# MCU.net
KiCad netlist of a schematic drawn in Altium Designer
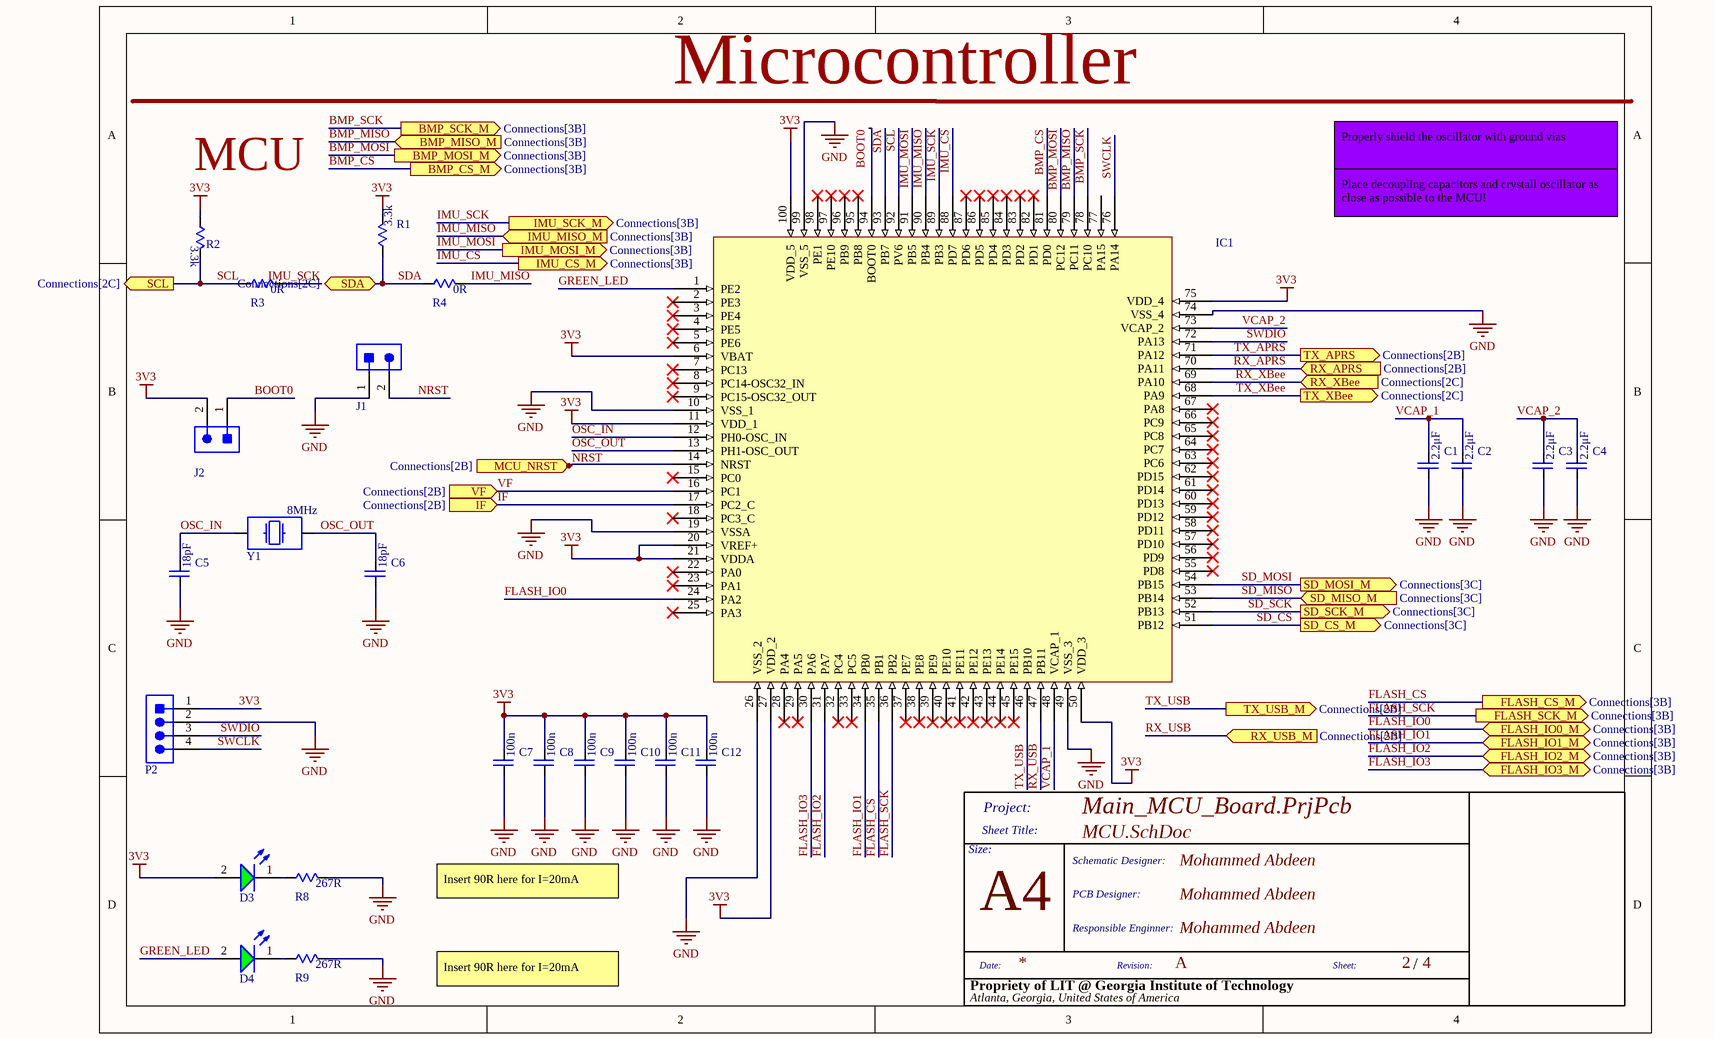
[diagram p0: MCU.SchDoc]

(export (version "E")
  (design (tool "Eeschema 10.0.6"))
  (components
    (comp (ref "C1")
      (value "CL10A225KO8NNNC")
      (footprint "0603-CAP")
      (description "2.2 µF ±10% 16V Ceramic Capacitor X5R 0603 (1608 Metric)")
      (fields (field (name "MANUFACTURER") "Samsung Electro-Mechanics"))
      (libsource (lib "MainMCUSch") (part "CAP-0603-16V"))
    )
    (comp (ref "C2")
      (value "CL10A225KO8NNNC")
      (footprint "0603-CAP")
      (description "2.2 µF ±10% 16V Ceramic Capacitor X5R 0603 (1608 Metric)")
      (fields (field (name "MANUFACTURER") "Samsung Electro-Mechanics"))
      (libsource (lib "MainMCUSch") (part "CAP-0603-16V"))
    )
    (comp (ref "C3")
      (value "CL10A225KO8NNNC")
      (footprint "0603-CAP")
      (description "2.2 µF ±10% 16V Ceramic Capacitor X5R 0603 (1608 Metric)")
      (fields (field (name "MANUFACTURER") "Samsung Electro-Mechanics"))
      (libsource (lib "MainMCUSch") (part "CAP-0603-16V"))
    )
    (comp (ref "C4")
      (value "CL10A225KO8NNNC")
      (footprint "0603-CAP")
      (description "2.2 µF ±10% 16V Ceramic Capacitor X5R 0603 (1608 Metric)")
      (fields (field (name "MANUFACTURER") "Samsung Electro-Mechanics"))
      (libsource (lib "MainMCUSch") (part "CAP-0603-16V"))
    )
    (comp (ref "C5")
      (value "600F180FT250XT")
      (footprint "CAP-0805")
      (description "18 pF ±1% 250V Ceramic Capacitor C0G, NP0 0805 (2012 Metric)")
      (libsource (lib "MainMCUSch") (part "CAP-0805-250V-18pF"))
    )
    (comp (ref "C6")
      (value "600F180FT250XT")
      (footprint "CAP-0805")
      (description "18 pF ±1% 250V Ceramic Capacitor C0G, NP0 0805 (2012 Metric)")
      (libsource (lib "MainMCUSch") (part "CAP-0805-250V-18pF"))
    )
    (comp (ref "C7")
      (value "KGM21NR71E104KT")
      (footprint "CAP-0805")
      (description "0.1 µF ±10% 25V Ceramic Capacitor X7R 0805 (2012 Metric)")
      (libsource (lib "MainMCUSch") (part "CAP-0805-25V-100n"))
    )
    (comp (ref "C8")
      (value "KGM21NR71E104KT")
      (footprint "CAP-0805")
      (description "0.1 µF ±10% 25V Ceramic Capacitor X7R 0805 (2012 Metric)")
      (libsource (lib "MainMCUSch") (part "CAP-0805-25V-100n"))
    )
    (comp (ref "C9")
      (value "KGM21NR71E104KT")
      (footprint "CAP-0805")
      (description "0.1 µF ±10% 25V Ceramic Capacitor X7R 0805 (2012 Metric)")
      (libsource (lib "MainMCUSch") (part "CAP-0805-25V-100n"))
    )
    (comp (ref "C10")
      (value "KGM21NR71E104KT")
      (footprint "CAP-0805")
      (description "0.1 µF ±10% 25V Ceramic Capacitor X7R 0805 (2012 Metric)")
      (libsource (lib "MainMCUSch") (part "CAP-0805-25V-100n"))
    )
    (comp (ref "C11")
      (value "KGM21NR71E104KT")
      (footprint "CAP-0805")
      (description "0.1 µF ±10% 25V Ceramic Capacitor X7R 0805 (2012 Metric)")
      (libsource (lib "MainMCUSch") (part "CAP-0805-25V-100n"))
    )
    (comp (ref "C12")
      (value "KGM21NR71E104KT")
      (footprint "CAP-0805")
      (description "0.1 µF ±10% 25V Ceramic Capacitor X7R 0805 (2012 Metric)")
      (libsource (lib "MainMCUSch") (part "CAP-0805-25V-100n"))
    )
    (comp (ref "D3")
      (value "LTST-C190KGKT")
      (footprint "FP-LTST-C190KGKT-MFG")
      (description "Green 571nm LED Indication - Discrete 2V 0603 (1608 Metric)")
      (libsource (lib "MainMCUSch") (part "LED-0603-Green_"))
    )
    (comp (ref "D4")
      (value "LTST-C190KGKT")
      (footprint "FP-LTST-C190KGKT-MFG")
      (description "Green 571nm LED Indication - Discrete 2V 0603 (1608 Metric)")
      (libsource (lib "MainMCUSch") (part "LED-0603-Green_"))
    )
    (comp (ref "IC1")
      (value "STM32H723VGT6")
      (footprint "QFP50P1600X1600X160-100N")
      (fields (field (name "MANUFACTURER") "STMicroelectronics"))
      (libsource (lib "MainMCUSch") (part "STMH723VGT6"))
    )
    (comp (ref "J1")
      (value "61300211121")
      (footprint "HEADER-2-Pin")
      (description "Connector Header Through Hole 2 position 0.100\" (2.54mm)")
      (fields (field (name "MANUFACTURER") "Würth Elektronik"))
      (libsource (lib "") (part "Header-2-Pin-Male_1"))
    )
    (comp (ref "J2")
      (value "61300211121")
      (footprint "HEADER-2-Pin")
      (description "Connector Header Through Hole 2 position 0.100\" (2.54mm)")
      (fields (field (name "MANUFACTURER") "Würth Elektronik"))
      (libsource (lib "MainMCUSch") (part "Header-2-Pin-Male"))
    )
    (comp (ref "P2")
      (value "22-27-2041")
      (footprint "MOLX-22-27-2041_V")
      (description "Male Header, Pitch 2.54 mm, 1 x 4 Position, Height 11.7 mm, Tail Length 3.56 mm, RoHS, Bulk")
      (fields (field (name "MANUFACTURER") "MOLEX"))
      (libsource (lib "MainMCUSch") (part "Header-4-Pin"))
    )
    (comp (ref "R1")
      (value "ERA-3AEB332V")
      (footprint "0603-RES")
      (description "3.3 kOhms ±0.1% 0.1W, 1/10W Chip Resistor 0603 (1608 Metric) Automotive AEC-Q200 Thin Film")
      (fields (field (name "MANUFACTURER") "Panasonic Electronic Components"))
      (libsource (lib "MainMCUSch") (part "RES-0603-3.3k"))
    )
    (comp (ref "R2")
      (value "ERA-3AEB332V")
      (footprint "0603-RES")
      (description "3.3 kOhms ±0.1% 0.1W, 1/10W Chip Resistor 0603 (1608 Metric) Automotive AEC-Q200 Thin Film")
      (fields (field (name "MANUFACTURER") "Panasonic Electronic Components"))
      (libsource (lib "MainMCUSch") (part "RES-0603-3.3k"))
    )
    (comp (ref "R3")
      (value "ERJ-6GEY0R00V")
      (footprint "0805-RES")
      (description "0 Ohms Jumper Chip Resistor 0805 (2012 Metric) Automotive AEC-Q200 Thick Film")
      (libsource (lib "MainMCUSch") (part "RES-0805-0R"))
    )
    (comp (ref "R4")
      (value "ERJ-6GEY0R00V")
      (footprint "0805-RES")
      (description "0 Ohms Jumper Chip Resistor 0805 (2012 Metric) Automotive AEC-Q200 Thick Film")
      (libsource (lib "MainMCUSch") (part "RES-0805-0R"))
    )
    (comp (ref "R8")
      (value "ERJ-3EKF2670V")
      (footprint "0603-RES")
      (description "267 Ohms ±1% 0.1W, 1/10W Chip Resistor 0603 (1608 Metric) Automotive AEC-Q200 Thick Film")
      (fields (field (name "MANUFACTURER") "Panasonic Electronic Components"))
      (libsource (lib "MainMCUSch") (part "RES-0603-267R"))
    )
    (comp (ref "R9")
      (value "ERJ-3EKF2670V")
      (footprint "0603-RES")
      (description "267 Ohms ±1% 0.1W, 1/10W Chip Resistor 0603 (1608 Metric) Automotive AEC-Q200 Thick Film")
      (fields (field (name "MANUFACTURER") "Panasonic Electronic Components"))
      (libsource (lib "MainMCUSch") (part "RES-0603-267R"))
    )
    (comp (ref "Y1")
      (value "ABLS-8.000MHZ-B2-T")
      (footprint "ABLS-8.000MHZ-B2-T")
      (description "8 MHz ±20ppm Crystal 18pF 80 Ohms HC-49/US")
      (libsource (lib "MainMCUSch") (part "OSC-8MHz-3V3"))
    )
  )
  (nets
    (net (code "1") (name "/BMP_CS") (class "Default")
      (node (ref "IC1") (pin "81") (pinfunction "PD0_81") (pintype "input"))
    )
    (net (code "2") (name "/BMP_MISO") (class "Default")
      (node (ref "IC1") (pin "79") (pinfunction "PC11_79") (pintype "input"))
    )
    (net (code "3") (name "/BMP_MOSI") (class "Default")
      (node (ref "IC1") (pin "80") (pinfunction "PC12_80") (pintype "input"))
    )
    (net (code "4") (name "/BMP_SCK") (class "Default")
      (node (ref "IC1") (pin "78") (pinfunction "PC10_78") (pintype "input"))
    )
    (net (code "5") (name "/BOOT0") (class "Default")
      (node (ref "IC1") (pin "94") (pinfunction "BOOT0_94") (pintype "input"))
      (node (ref "J2") (pin "1") (pinfunction "1_1") (pintype "passive"))
    )
    (net (code "6") (name "/FLASH_CS") (class "Default")
      (node (ref "IC1") (pin "35") (pinfunction "PB1_35") (pintype "input"))
    )
    (net (code "7") (name "/FLASH_IO0") (class "Default")
      (node (ref "IC1") (pin "24") (pinfunction "PA2_24") (pintype "input"))
    )
    (net (code "8") (name "/FLASH_IO1") (class "Default")
      (node (ref "IC1") (pin "34") (pinfunction "PB0_34") (pintype "input"))
    )
    (net (code "9") (name "/FLASH_IO2") (class "Default")
      (node (ref "IC1") (pin "31") (pinfunction "PA7_31") (pintype "input"))
    )
    (net (code "10") (name "/FLASH_IO3") (class "Default")
      (node (ref "IC1") (pin "30") (pinfunction "PA6_30") (pintype "input"))
    )
    (net (code "11") (name "/FLASH_SCK") (class "Default")
      (node (ref "IC1") (pin "36") (pinfunction "PB2_36") (pintype "input"))
    )
    (net (code "12") (name "/GREEN_LED") (class "Default")
      (node (ref "D4") (pin "2") (pinfunction "A_2") (pintype "passive"))
      (node (ref "IC1") (pin "1") (pinfunction "PE2_1") (pintype "input"))
    )
    (net (code "13") (name "/IF") (class "Default")
      (node (ref "IC1") (pin "17") (pinfunction "PC2_C_17") (pintype "input"))
    )
    (net (code "14") (name "/IMU_CS") (class "Default")
      (node (ref "IC1") (pin "88") (pinfunction "PD7_88") (pintype "input"))
    )
    (net (code "15") (name "/IMU_MISO") (class "Default")
      (node (ref "IC1") (pin "90") (pinfunction "PB4_90") (pintype "input"))
      (node (ref "R4") (pin "2") (pintype "passive"))
    )
    (net (code "16") (name "/IMU_MOSI") (class "Default")
      (node (ref "IC1") (pin "91") (pinfunction "PB5_91") (pintype "input"))
    )
    (net (code "17") (name "/IMU_SCK") (class "Default")
      (node (ref "IC1") (pin "89") (pinfunction "PB3_89") (pintype "input"))
      (node (ref "R3") (pin "2") (pintype "passive"))
    )
    (net (code "18") (name "/NRST") (class "Default")
      (node (ref "IC1") (pin "14") (pinfunction "NRST_14") (pintype "input"))
      (node (ref "J1") (pin "2") (pinfunction "2_2") (pintype "passive"))
    )
    (net (code "19") (name "/OSC_IN") (class "Default")
      (node (ref "C5") (pin "2") (pintype "passive"))
      (node (ref "IC1") (pin "12") (pinfunction "PH0-OSC_IN_12") (pintype "input"))
      (node (ref "Y1") (pin "1") (pintype "passive"))
    )
    (net (code "20") (name "/OSC_OUT") (class "Default")
      (node (ref "C6") (pin "2") (pintype "passive"))
      (node (ref "IC1") (pin "13") (pinfunction "PH1-OSC_OUT_13") (pintype "input"))
      (node (ref "Y1") (pin "2") (pintype "passive"))
    )
    (net (code "21") (name "/RX_APRS") (class "Default")
      (node (ref "IC1") (pin "70") (pinfunction "PA11_70") (pintype "input"))
    )
    (net (code "22") (name "/RX_USB") (class "Default")
      (node (ref "IC1") (pin "47") (pinfunction "PB11_47") (pintype "input"))
    )
    (net (code "23") (name "/RX_XBee") (class "Default")
      (node (ref "IC1") (pin "69") (pinfunction "PA10_69") (pintype "input"))
    )
    (net (code "24") (name "/SCL") (class "Default")
      (node (ref "IC1") (pin "92") (pinfunction "PV6_92") (pintype "input"))
      (node (ref "R2") (pin "2") (pintype "passive"))
      (node (ref "R3") (pin "1") (pintype "passive"))
    )
    (net (code "25") (name "/SDA") (class "Default")
      (node (ref "IC1") (pin "93") (pinfunction "PB7_93") (pintype "input"))
      (node (ref "R1") (pin "1") (pintype "passive"))
      (node (ref "R4") (pin "1") (pintype "passive"))
    )
    (net (code "26") (name "/SD_CS") (class "Default")
      (node (ref "IC1") (pin "51") (pinfunction "PB12_51") (pintype "input"))
    )
    (net (code "27") (name "/SD_MISO") (class "Default")
      (node (ref "IC1") (pin "53") (pinfunction "PB14_53") (pintype "input"))
    )
    (net (code "28") (name "/SD_MOSI") (class "Default")
      (node (ref "IC1") (pin "54") (pinfunction "PB15_54") (pintype "input"))
    )
    (net (code "29") (name "/SD_SCK") (class "Default")
      (node (ref "IC1") (pin "52") (pinfunction "PB13_52") (pintype "input"))
    )
    (net (code "30") (name "/SWCLK") (class "Default")
      (node (ref "IC1") (pin "76") (pinfunction "PA14_76") (pintype "input"))
      (node (ref "P2") (pin "4") (pinfunction "4_4") (pintype "passive"))
    )
    (net (code "31") (name "/SWDIO") (class "Default")
      (node (ref "IC1") (pin "72") (pinfunction "PA13_72") (pintype "input"))
      (node (ref "P2") (pin "3") (pinfunction "3_3") (pintype "passive"))
    )
    (net (code "32") (name "/TX_APRS") (class "Default")
      (node (ref "IC1") (pin "71") (pinfunction "PA12_71") (pintype "input"))
    )
    (net (code "33") (name "/TX_USB") (class "Default")
      (node (ref "IC1") (pin "46") (pinfunction "PB10_46") (pintype "input"))
    )
    (net (code "34") (name "/TX_XBee") (class "Default")
      (node (ref "IC1") (pin "68") (pinfunction "PA9_68") (pintype "input"))
    )
    (net (code "35") (name "/VCAP_1") (class "Default")
      (node (ref "C1") (pin "2") (pintype "passive"))
      (node (ref "C2") (pin "2") (pintype "passive"))
      (node (ref "IC1") (pin "48") (pinfunction "VCAP_1_48") (pintype "input"))
    )
    (net (code "36") (name "/VCAP_2") (class "Default")
      (node (ref "C3") (pin "2") (pintype "passive"))
      (node (ref "C4") (pin "2") (pintype "passive"))
      (node (ref "IC1") (pin "73") (pinfunction "VCAP_2_73") (pintype "input"))
    )
    (net (code "37") (name "/VF") (class "Default")
      (node (ref "IC1") (pin "16") (pinfunction "PC1_16") (pintype "input"))
    )
    (net (code "38") (name "3V3") (class "Default")
      (node (ref "C10") (pin "2") (pintype "passive"))
      (node (ref "C11") (pin "2") (pintype "passive"))
      (node (ref "C12") (pin "2") (pintype "passive"))
      (node (ref "C7") (pin "2") (pintype "passive"))
      (node (ref "C8") (pin "2") (pintype "passive"))
      (node (ref "C9") (pin "2") (pintype "passive"))
      (node (ref "D3") (pin "2") (pinfunction "A_2") (pintype "passive"))
      (node (ref "IC1") (pin "100") (pinfunction "VDD_5_100") (pintype "input"))
      (node (ref "IC1") (pin "11") (pinfunction "VDD_1_11") (pintype "input"))
      (node (ref "IC1") (pin "20") (pinfunction "VREF+_20") (pintype "input"))
      (node (ref "IC1") (pin "21") (pinfunction "VDDA_21") (pintype "input"))
      (node (ref "IC1") (pin "27") (pinfunction "VDD_2_27") (pintype "input"))
      (node (ref "IC1") (pin "50") (pinfunction "VDD_3_50") (pintype "input"))
      (node (ref "IC1") (pin "6") (pinfunction "VBAT_6") (pintype "input"))
      (node (ref "IC1") (pin "75") (pinfunction "VDD_4_75") (pintype "input"))
      (node (ref "J2") (pin "2") (pinfunction "2_2") (pintype "passive"))
      (node (ref "P2") (pin "1") (pinfunction "1_1") (pintype "passive"))
      (node (ref "R1") (pin "2") (pintype "passive"))
      (node (ref "R2") (pin "1") (pintype "passive"))
    )
    (net (code "39") (name "GND") (class "Default")
      (node (ref "C1") (pin "1") (pintype "passive"))
      (node (ref "C10") (pin "1") (pintype "passive"))
      (node (ref "C11") (pin "1") (pintype "passive"))
      (node (ref "C12") (pin "1") (pintype "passive"))
      (node (ref "C2") (pin "1") (pintype "passive"))
      (node (ref "C3") (pin "1") (pintype "passive"))
      (node (ref "C4") (pin "1") (pintype "passive"))
      (node (ref "C5") (pin "1") (pintype "passive"))
      (node (ref "C6") (pin "1") (pintype "passive"))
      (node (ref "C7") (pin "1") (pintype "passive"))
      (node (ref "C8") (pin "1") (pintype "passive"))
      (node (ref "C9") (pin "1") (pintype "passive"))
      (node (ref "IC1") (pin "10") (pinfunction "VSS_1_10") (pintype "input"))
      (node (ref "IC1") (pin "19") (pinfunction "VSSA_19") (pintype "input"))
      (node (ref "IC1") (pin "26") (pinfunction "VSS_2_26") (pintype "input"))
      (node (ref "IC1") (pin "49") (pinfunction "VSS_3_49") (pintype "input"))
      (node (ref "IC1") (pin "74") (pinfunction "VSS_4_74") (pintype "input"))
      (node (ref "IC1") (pin "99") (pinfunction "VSS_5_99") (pintype "input"))
      (node (ref "J1") (pin "1") (pinfunction "1_1") (pintype "passive"))
      (node (ref "P2") (pin "2") (pinfunction "2_2") (pintype "passive"))
      (node (ref "R8") (pin "2") (pintype "passive"))
      (node (ref "R9") (pin "2") (pintype "passive"))
    )
    (net (code "40") (name "Net-(D3-K)") (class "Default")
      (node (ref "D3") (pin "1") (pinfunction "K_1") (pintype "passive"))
      (node (ref "R8") (pin "1") (pintype "passive"))
    )
    (net (code "41") (name "Net-(D4-K)") (class "Default")
      (node (ref "D4") (pin "1") (pinfunction "K_1") (pintype "passive"))
      (node (ref "R9") (pin "1") (pintype "passive"))
    )
    (net (code "42") (name "unconnected-(IC1-PA0-Pad22)") (class "Default")
      (node (ref "IC1") (pin "22") (pinfunction "PA0_22") (pintype "input+no_connect"))
    )
    (net (code "43") (name "unconnected-(IC1-PA1-Pad23)") (class "Default")
      (node (ref "IC1") (pin "23") (pinfunction "PA1_23") (pintype "input+no_connect"))
    )
    (net (code "44") (name "unconnected-(IC1-PA3-Pad25)") (class "Default")
      (node (ref "IC1") (pin "25") (pinfunction "PA3_25") (pintype "input+no_connect"))
    )
    (net (code "45") (name "unconnected-(IC1-PA4-Pad28)") (class "Default")
      (node (ref "IC1") (pin "28") (pinfunction "PA4_28") (pintype "input+no_connect"))
    )
    (net (code "46") (name "unconnected-(IC1-PA5-Pad29)") (class "Default")
      (node (ref "IC1") (pin "29") (pinfunction "PA5_29") (pintype "input+no_connect"))
    )
    (net (code "47") (name "unconnected-(IC1-PA8-Pad67)") (class "Default")
      (node (ref "IC1") (pin "67") (pinfunction "PA8_67") (pintype "input+no_connect"))
    )
    (net (code "48") (name "unconnected-(IC1-PA15-Pad77)") (class "Default")
      (node (ref "IC1") (pin "77") (pinfunction "PA15_77") (pintype "input"))
    )
    (net (code "49") (name "unconnected-(IC1-PB8-Pad95)") (class "Default")
      (node (ref "IC1") (pin "95") (pinfunction "PB8_95") (pintype "input+no_connect"))
    )
    (net (code "50") (name "unconnected-(IC1-PB9-Pad96)") (class "Default")
      (node (ref "IC1") (pin "96") (pinfunction "PB9_96") (pintype "input+no_connect"))
    )
    (net (code "51") (name "unconnected-(IC1-PC0-Pad15)") (class "Default")
      (node (ref "IC1") (pin "15") (pinfunction "PC0_15") (pintype "input+no_connect"))
    )
    (net (code "52") (name "unconnected-(IC1-PC3_C-Pad18)") (class "Default")
      (node (ref "IC1") (pin "18") (pinfunction "PC3_C_18") (pintype "input+no_connect"))
    )
    (net (code "53") (name "unconnected-(IC1-PC4-Pad32)") (class "Default")
      (node (ref "IC1") (pin "32") (pinfunction "PC4_32") (pintype "input+no_connect"))
    )
    (net (code "54") (name "unconnected-(IC1-PC5-Pad33)") (class "Default")
      (node (ref "IC1") (pin "33") (pinfunction "PC5_33") (pintype "input+no_connect"))
    )
    (net (code "55") (name "unconnected-(IC1-PC6-Pad63)") (class "Default")
      (node (ref "IC1") (pin "63") (pinfunction "PC6_63") (pintype "input+no_connect"))
    )
    (net (code "56") (name "unconnected-(IC1-PC7-Pad64)") (class "Default")
      (node (ref "IC1") (pin "64") (pinfunction "PC7_64") (pintype "input+no_connect"))
    )
    (net (code "57") (name "unconnected-(IC1-PC8-Pad65)") (class "Default")
      (node (ref "IC1") (pin "65") (pinfunction "PC8_65") (pintype "input+no_connect"))
    )
    (net (code "58") (name "unconnected-(IC1-PC9-Pad66)") (class "Default")
      (node (ref "IC1") (pin "66") (pinfunction "PC9_66") (pintype "input+no_connect"))
    )
    (net (code "59") (name "unconnected-(IC1-PC13-Pad7)") (class "Default")
      (node (ref "IC1") (pin "7") (pinfunction "PC13_7") (pintype "input+no_connect"))
    )
    (net (code "60") (name "unconnected-(IC1-PC14-OSC32_IN-Pad8)") (class "Default")
      (node (ref "IC1") (pin "8") (pinfunction "PC14-OSC32_IN_8") (pintype "input+no_connect"))
    )
    (net (code "61") (name "unconnected-(IC1-PC15-OSC32_OUT-Pad9)") (class "Default")
      (node (ref "IC1") (pin "9") (pinfunction "PC15-OSC32_OUT_9") (pintype "input+no_connect"))
    )
    (net (code "62") (name "unconnected-(IC1-PD1-Pad82)") (class "Default")
      (node (ref "IC1") (pin "82") (pinfunction "PD1_82") (pintype "input+no_connect"))
    )
    (net (code "63") (name "unconnected-(IC1-PD2-Pad83)") (class "Default")
      (node (ref "IC1") (pin "83") (pinfunction "PD2_83") (pintype "input+no_connect"))
    )
    (net (code "64") (name "unconnected-(IC1-PD3-Pad84)") (class "Default")
      (node (ref "IC1") (pin "84") (pinfunction "PD3_84") (pintype "input+no_connect"))
    )
    (net (code "65") (name "unconnected-(IC1-PD4-Pad85)") (class "Default")
      (node (ref "IC1") (pin "85") (pinfunction "PD4_85") (pintype "input+no_connect"))
    )
    (net (code "66") (name "unconnected-(IC1-PD5-Pad86)") (class "Default")
      (node (ref "IC1") (pin "86") (pinfunction "PD5_86") (pintype "input+no_connect"))
    )
    (net (code "67") (name "unconnected-(IC1-PD6-Pad87)") (class "Default")
      (node (ref "IC1") (pin "87") (pinfunction "PD6_87") (pintype "input+no_connect"))
    )
    (net (code "68") (name "unconnected-(IC1-PD8-Pad55)") (class "Default")
      (node (ref "IC1") (pin "55") (pinfunction "PD8_55") (pintype "input+no_connect"))
    )
    (net (code "69") (name "unconnected-(IC1-PD9-Pad56)") (class "Default")
      (node (ref "IC1") (pin "56") (pinfunction "PD9_56") (pintype "input+no_connect"))
    )
    (net (code "70") (name "unconnected-(IC1-PD10-Pad57)") (class "Default")
      (node (ref "IC1") (pin "57") (pinfunction "PD10_57") (pintype "input+no_connect"))
    )
    (net (code "71") (name "unconnected-(IC1-PD11-Pad58)") (class "Default")
      (node (ref "IC1") (pin "58") (pinfunction "PD11_58") (pintype "input+no_connect"))
    )
    (net (code "72") (name "unconnected-(IC1-PD12-Pad59)") (class "Default")
      (node (ref "IC1") (pin "59") (pinfunction "PD12_59") (pintype "input+no_connect"))
    )
    (net (code "73") (name "unconnected-(IC1-PD13-Pad60)") (class "Default")
      (node (ref "IC1") (pin "60") (pinfunction "PD13_60") (pintype "input+no_connect"))
    )
    (net (code "74") (name "unconnected-(IC1-PD14-Pad61)") (class "Default")
      (node (ref "IC1") (pin "61") (pinfunction "PD14_61") (pintype "input+no_connect"))
    )
    (net (code "75") (name "unconnected-(IC1-PD15-Pad62)") (class "Default")
      (node (ref "IC1") (pin "62") (pinfunction "PD15_62") (pintype "input+no_connect"))
    )
    (net (code "76") (name "unconnected-(IC1-PE1-Pad98)") (class "Default")
      (node (ref "IC1") (pin "98") (pinfunction "PE1_98") (pintype "input+no_connect"))
    )
    (net (code "77") (name "unconnected-(IC1-PE3-Pad2)") (class "Default")
      (node (ref "IC1") (pin "2") (pinfunction "PE3_2") (pintype "input+no_connect"))
    )
    (net (code "78") (name "unconnected-(IC1-PE4-Pad3)") (class "Default")
      (node (ref "IC1") (pin "3") (pinfunction "PE4_3") (pintype "input+no_connect"))
    )
    (net (code "79") (name "unconnected-(IC1-PE5-Pad4)") (class "Default")
      (node (ref "IC1") (pin "4") (pinfunction "PE5_4") (pintype "input+no_connect"))
    )
    (net (code "80") (name "unconnected-(IC1-PE6-Pad5)") (class "Default")
      (node (ref "IC1") (pin "5") (pinfunction "PE6_5") (pintype "input+no_connect"))
    )
    (net (code "81") (name "unconnected-(IC1-PE7-Pad37)") (class "Default")
      (node (ref "IC1") (pin "37") (pinfunction "PE7_37") (pintype "input+no_connect"))
    )
    (net (code "82") (name "unconnected-(IC1-PE8-Pad38)") (class "Default")
      (node (ref "IC1") (pin "38") (pinfunction "PE8_38") (pintype "input+no_connect"))
    )
    (net (code "83") (name "unconnected-(IC1-PE9-Pad39)") (class "Default")
      (node (ref "IC1") (pin "39") (pinfunction "PE9_39") (pintype "input+no_connect"))
    )
    (net (code "84") (name "unconnected-(IC1-PE10-Pad40)") (class "Default")
      (node (ref "IC1") (pin "40") (pinfunction "PE10_40") (pintype "input+no_connect"))
    )
    (net (code "85") (name "unconnected-(IC1-PE10-Pad97)") (class "Default")
      (node (ref "IC1") (pin "97") (pinfunction "PE10_97") (pintype "input+no_connect"))
    )
    (net (code "86") (name "unconnected-(IC1-PE11-Pad41)") (class "Default")
      (node (ref "IC1") (pin "41") (pinfunction "PE11_41") (pintype "input+no_connect"))
    )
    (net (code "87") (name "unconnected-(IC1-PE12-Pad42)") (class "Default")
      (node (ref "IC1") (pin "42") (pinfunction "PE12_42") (pintype "input+no_connect"))
    )
    (net (code "88") (name "unconnected-(IC1-PE13-Pad43)") (class "Default")
      (node (ref "IC1") (pin "43") (pinfunction "PE13_43") (pintype "input+no_connect"))
    )
    (net (code "89") (name "unconnected-(IC1-PE14-Pad44)") (class "Default")
      (node (ref "IC1") (pin "44") (pinfunction "PE14_44") (pintype "input+no_connect"))
    )
    (net (code "90") (name "unconnected-(IC1-PE15-Pad45)") (class "Default")
      (node (ref "IC1") (pin "45") (pinfunction "PE15_45") (pintype "input+no_connect"))
    )
  )
)
